# Mainboard-mbed.net
KiCad netlist of a schematic drawn in Altium Designer
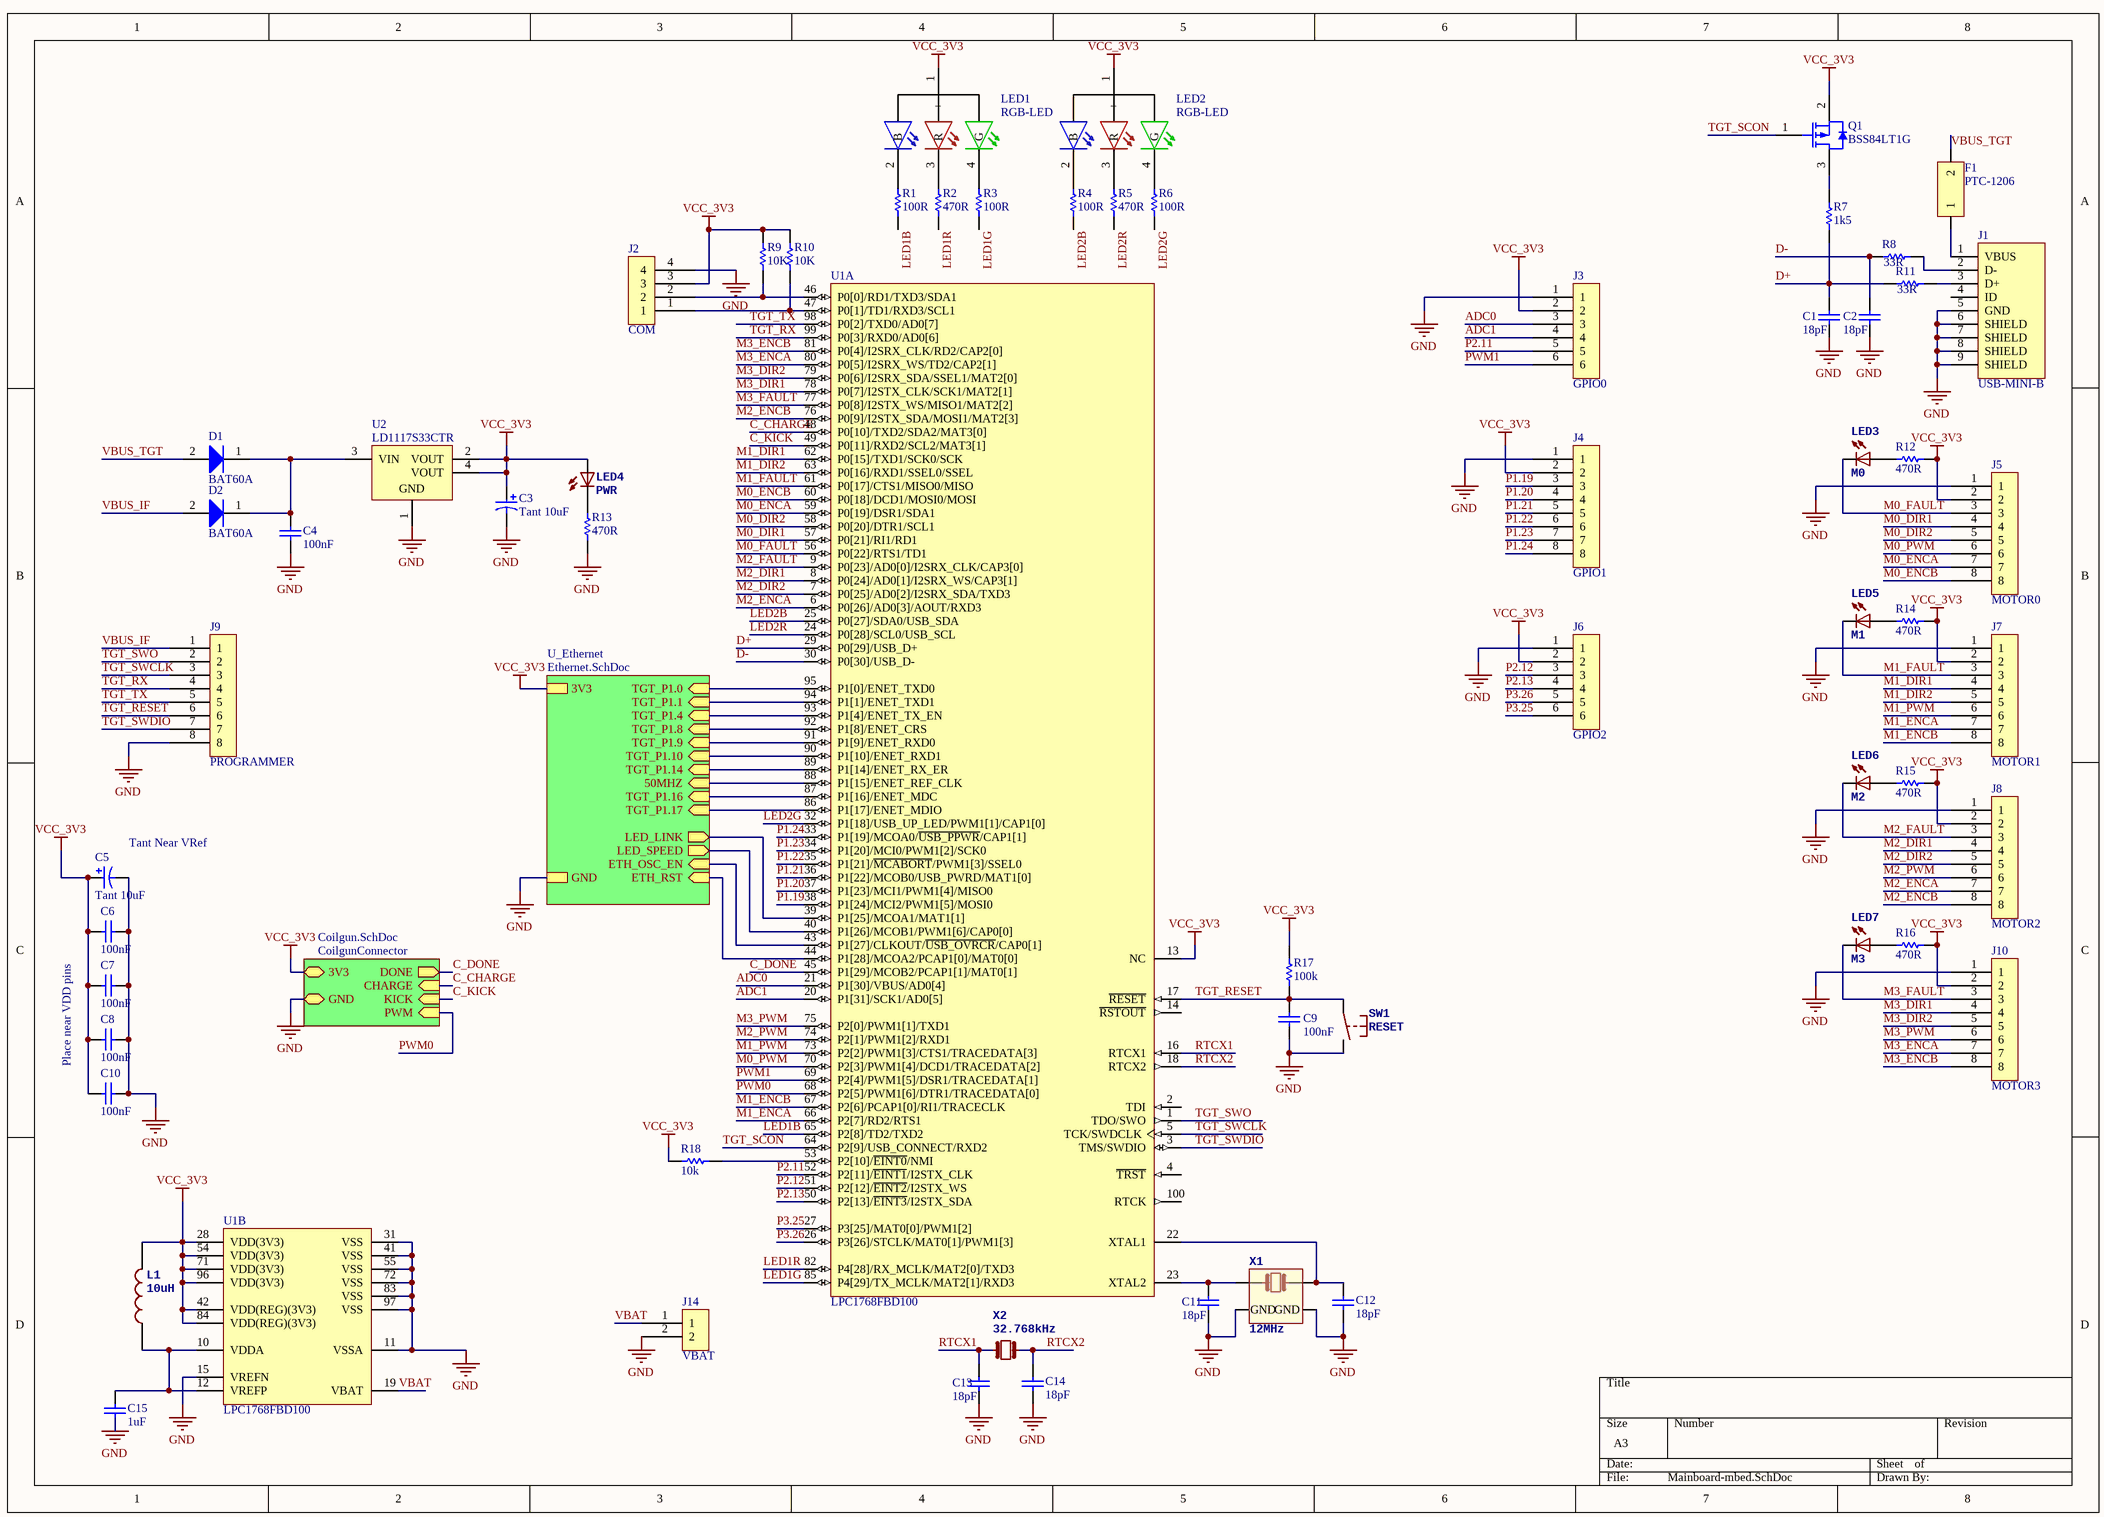
[diagram p0: Mainboard-mbed.SchDoc]

(export (version "E")
  (design (tool "Eeschema 10.0.6"))
  (components
    (comp (ref "C1")
      (value "18pF")
      (footprint "CAPC0603(1608)100_L")
      (description "0603 (1608 Metric) Chip Capacitor")
      (fields (field (name "Comment") "CAP0603"))
      (libsource (lib "Altium Content Vault") (part "CMP-1590-00005-1"))
    )
    (comp (ref "C2")
      (value "18pF")
      (footprint "CAPC0603(1608)100_L")
      (description "0603 (1608 Metric) Chip Capacitor")
      (fields (field (name "Comment") "CAP0603"))
      (libsource (lib "Altium Content Vault") (part "CMP-1590-00005-1"))
    )
    (comp (ref "C3")
      (value "Tant 10uF")
      (footprint "CAPMP3528X12N")
      (libsource (lib "passive") (part "cap_pol"))
    )
    (comp (ref "C4")
      (value "100nF")
      (footprint "CAPC0603(1608)100_L")
      (description "0603 (1608 Metric) Chip Capacitor")
      (fields (field (name "Comment") "CAP0603"))
      (libsource (lib "Altium Content Vault") (part "CMP-1590-00005-1"))
    )
    (comp (ref "C5")
      (value "Tant 10uF")
      (footprint "CAPMP3528X12N")
      (libsource (lib "passive") (part "cap_pol"))
    )
    (comp (ref "C6")
      (value "100nF")
      (footprint "CAPC0603(1608)100_L")
      (description "CAP 100nF 10V ±5% 0603 (1608 Metric) Thickness 1mm SMD")
      (fields (field (name "TOLERANCE") "Â±5%"))
      (libsource (lib "Altium Content Vault") (part "CMP-1035-02579-1"))
    )
    (comp (ref "C7")
      (value "100nF")
      (footprint "CAPC0603(1608)100_L")
      (description "CAP 100nF 10V ±5% 0603 (1608 Metric) Thickness 1mm SMD")
      (fields (field (name "TOLERANCE") "Â±5%"))
      (libsource (lib "Altium Content Vault") (part "CMP-1035-02579-1"))
    )
    (comp (ref "C8")
      (value "100nF")
      (footprint "CAPC0603(1608)100_L")
      (description "CAP 100nF 10V ±5% 0603 (1608 Metric) Thickness 1mm SMD")
      (fields (field (name "TOLERANCE") "Â±5%"))
      (libsource (lib "Altium Content Vault") (part "CMP-1035-02579-1"))
    )
    (comp (ref "C9")
      (value "100nF")
      (footprint "CAPC0603(1608)100_L")
      (description "0603 (1608 Metric) Chip Capacitor")
      (fields (field (name "Comment") "CAP0603"))
      (libsource (lib "Altium Content Vault") (part "CMP-1590-00005-1"))
    )
    (comp (ref "C10")
      (value "100nF")
      (footprint "CAPC0603(1608)100_L")
      (description "CAP 100nF 10V ±5% 0603 (1608 Metric) Thickness 1mm SMD")
      (fields (field (name "TOLERANCE") "Â±5%"))
      (libsource (lib "Altium Content Vault") (part "CMP-1035-02579-1"))
    )
    (comp (ref "C11")
      (value "18pF")
      (footprint "CAPC0603(1608)100_L")
      (description "0603 (1608 Metric) Chip Capacitor")
      (fields (field (name "Comment") "CAP0603"))
      (libsource (lib "Altium Content Vault") (part "CMP-1590-00005-1"))
    )
    (comp (ref "C12")
      (value "18pF")
      (footprint "CAPC0603(1608)100_L")
      (description "0603 (1608 Metric) Chip Capacitor")
      (fields (field (name "Comment") "CAP0603"))
      (libsource (lib "Altium Content Vault") (part "CMP-1590-00005-1"))
    )
    (comp (ref "C13")
      (value "18pF")
      (footprint "CAPC0603(1608)100_L")
      (description "0603 (1608 Metric) Chip Capacitor")
      (fields (field (name "Comment") "CAP0603"))
      (libsource (lib "Altium Content Vault") (part "CMP-1590-00005-1"))
    )
    (comp (ref "C14")
      (value "18pF")
      (footprint "CAPC0603(1608)100_L")
      (description "0603 (1608 Metric) Chip Capacitor")
      (fields (field (name "Comment") "CAP0603"))
      (libsource (lib "Altium Content Vault") (part "CMP-1590-00005-1"))
    )
    (comp (ref "C15")
      (value "1uF")
      (footprint "CAPC0603(1608)100_L")
      (description "0603 (1608 Metric) Chip Capacitor")
      (fields (field (name "Comment") "CAP0603"))
      (libsource (lib "Altium Content Vault") (part "CMP-1590-00005-1"))
    )
    (comp (ref "D1")
      (value "BAT60A")
      (footprint "INF-SOD323_V")
      (description "Silicon Schottky Diode, -55 to 85 degC, SOD323, Reel, Green")
      (fields (field (name "MANUFACTURER") "Infineon"))
      (libsource (lib "Altium Content Vault") (part "INF-D_K1A2-2"))
    )
    (comp (ref "D2")
      (value "BAT60A")
      (footprint "INF-SOD323_V")
      (description "Silicon Schottky Diode, -55 to 85 degC, SOD323, Reel, Green")
      (fields (field (name "MANUFACTURER") "Infineon"))
      (libsource (lib "Altium Content Vault") (part "INF-D_K1A2-2"))
    )
    (comp (ref "F1") (value "PTC-1206") (footprint "PTC-1206") (libsource (lib "power") (part "PTC-1206")))
    (comp (ref "J1")
      (value "USB-MINI-B")
      (footprint "USB-B-MINI")
      (libsource (lib "connectors") (part "USB-B-MINI"))
    )
    (comp (ref "J2")
      (value "COM")
      (footprint "MICRO-MATCH-4")
      (libsource (lib "connectors") (part "HEADER-4"))
    )
    (comp (ref "J3")
      (value "GPIO0")
      (footprint "MICRO-MATCH-6")
      (libsource (lib "connectors") (part "HEADER-6"))
    )
    (comp (ref "J4")
      (value "GPIO1")
      (footprint "MICRO-MATCH-8")
      (libsource (lib "connectors") (part "HEADER-8"))
    )
    (comp (ref "J5")
      (value "MOTOR0")
      (footprint "MICRO-MATCH-8")
      (libsource (lib "connectors") (part "HEADER-8"))
    )
    (comp (ref "J6")
      (value "GPIO2")
      (footprint "MICRO-MATCH-6")
      (libsource (lib "connectors") (part "HEADER-6"))
    )
    (comp (ref "J7")
      (value "MOTOR1")
      (footprint "MICRO-MATCH-8")
      (libsource (lib "connectors") (part "HEADER-8"))
    )
    (comp (ref "J8")
      (value "MOTOR2")
      (footprint "MICRO-MATCH-8")
      (libsource (lib "connectors") (part "HEADER-8"))
    )
    (comp (ref "J9")
      (value "PROGRAMMER")
      (footprint "MICRO-MATCH-8")
      (libsource (lib "connectors") (part "HEADER-8"))
    )
    (comp (ref "J10")
      (value "MOTOR3")
      (footprint "MICRO-MATCH-8")
      (libsource (lib "connectors") (part "HEADER-8"))
    )
    (comp (ref "J14")
      (value "VBAT")
      (footprint "PIN-HEADER-2")
      (libsource (lib "connectors") (part "HEADER-2"))
    )
    (comp (ref "L1") (value "10uH") (footprint "0603") (libsource (lib "mbed-HDK") (part "L")))
    (comp (ref "LED1") (value "RGB-LED") (footprint "RGB-LED") (libsource (lib "misc") (part "RGB-LED")))
    (comp (ref "LED2") (value "RGB-LED") (footprint "RGB-LED") (libsource (lib "misc") (part "RGB-LED")))
    (comp (ref "LED3") (value "M0") (footprint "CHIPLED_0603") (libsource (lib "mbed-HDK") (part "LED0603")))
    (comp (ref "LED4") (value "PWR") (footprint "CHIPLED_0603") (libsource (lib "mbed-HDK") (part "LED0603")))
    (comp (ref "LED5") (value "M1") (footprint "CHIPLED_0603") (libsource (lib "mbed-HDK") (part "LED0603")))
    (comp (ref "LED6") (value "M2") (footprint "CHIPLED_0603") (libsource (lib "mbed-HDK") (part "LED0603")))
    (comp (ref "LED7") (value "M3") (footprint "CHIPLED_0603") (libsource (lib "mbed-HDK") (part "LED0603")))
    (comp (ref "Q1")
      (value "BSS84LT1G")
      (footprint "ONSC-SOT-23-3-318-08_V")
      (description "Power MOSFET Single P-Channel, -50 V, 10 Ohm, 3-Pin SOT-23, Pb-Free, Tape and Reel")
      (fields (field (name "MANUFACTURER") "On Semiconductor"))
      (libsource (lib "Altium Content Vault") (part "CMP-1058-00762-1"))
    )
    (comp (ref "R1")
      (value "100R")
      (footprint "RESC0603(1608)_L")
      (fields (field (name "TOLERANCE") "5 %") (field (name "POWER") "0.1 W"))
      (libsource (lib "Altium Content Vault") (part "CMP-1012-00050-1"))
    )
    (comp (ref "R2")
      (value "470R")
      (footprint "RESC0603(1608)_L")
      (description "470R 0.1W 5% 0603 (1608 Metric)  SMD")
      (fields (field (name "TOLERANCE") "5 %") (field (name "POWER") "0.1 W"))
      (libsource (lib "Altium Content Vault") (part "CMP-1012-00066-1"))
    )
    (comp (ref "R3")
      (value "100R")
      (footprint "RESC0603(1608)_L")
      (fields (field (name "TOLERANCE") "5 %") (field (name "POWER") "0.1 W"))
      (libsource (lib "Altium Content Vault") (part "CMP-1012-00050-1"))
    )
    (comp (ref "R4")
      (value "100R")
      (footprint "RESC0603(1608)_L")
      (fields (field (name "TOLERANCE") "5 %") (field (name "POWER") "0.1 W"))
      (libsource (lib "Altium Content Vault") (part "CMP-1012-00050-1"))
    )
    (comp (ref "R5")
      (value "470R")
      (footprint "RESC0603(1608)_L")
      (description "470R 0.1W 5% 0603 (1608 Metric)  SMD")
      (fields (field (name "TOLERANCE") "5 %") (field (name "POWER") "0.1 W"))
      (libsource (lib "Altium Content Vault") (part "CMP-1012-00066-1"))
    )
    (comp (ref "R6")
      (value "100R")
      (footprint "RESC0603(1608)_L")
      (fields (field (name "TOLERANCE") "5 %") (field (name "POWER") "0.1 W"))
      (libsource (lib "Altium Content Vault") (part "CMP-1012-00050-1"))
    )
    (comp (ref "R7")
      (value "1k5")
      (footprint "RESC0603(1608)_L")
      (description "0603 (1608 Metric) Chip Resistor")
      (fields (field (name "Comment") "RES0603"))
      (libsource (lib "Altium Content Vault") (part "CMP-1591-00001-1"))
    )
    (comp (ref "R8")
      (value "33R")
      (footprint "RESC0603(1608)_L")
      (description "0603 (1608 Metric) Chip Resistor")
      (fields (field (name "Comment") "RES0603"))
      (libsource (lib "Altium Content Vault") (part "CMP-1591-00001-1"))
    )
    (comp (ref "R9")
      (value "10K")
      (footprint "RESC0603(1608)_L")
      (fields (field (name "TOLERANCE") "5 %") (field (name "POWER") "0.1 W"))
      (libsource (lib "Altium Content Vault") (part "CMP-1012-00098-1"))
    )
    (comp (ref "R10")
      (value "10K")
      (footprint "RESC0603(1608)_L")
      (fields (field (name "TOLERANCE") "5 %") (field (name "POWER") "0.1 W"))
      (libsource (lib "Altium Content Vault") (part "CMP-1012-00098-1"))
    )
    (comp (ref "R11")
      (value "33R")
      (footprint "RESC0603(1608)_L")
      (description "0603 (1608 Metric) Chip Resistor")
      (fields (field (name "Comment") "RES0603"))
      (libsource (lib "Altium Content Vault") (part "CMP-1591-00001-1"))
    )
    (comp (ref "R12")
      (value "470R")
      (footprint "RESC0603(1608)_N")
      (description "470R 0.1W 5% 0603 (1608 Metric)  SMD")
      (fields (field (name "TOLERANCE") "5 %") (field (name "POWER") "0.1 W"))
      (libsource (lib "Altium Content Vault") (part "CMP-1012-00066-1"))
    )
    (comp (ref "R13")
      (value "470R")
      (footprint "RESC0603(1608)_L")
      (description "470R 0.1W 5% 0603 (1608 Metric)  SMD")
      (fields (field (name "TOLERANCE") "5 %") (field (name "POWER") "0.1 W"))
      (libsource (lib "Altium Content Vault") (part "CMP-1012-00066-1"))
    )
    (comp (ref "R14")
      (value "470R")
      (footprint "RESC0603(1608)_N")
      (description "470R 0.1W 5% 0603 (1608 Metric)  SMD")
      (fields (field (name "TOLERANCE") "5 %") (field (name "POWER") "0.1 W"))
      (libsource (lib "Altium Content Vault") (part "CMP-1012-00066-1"))
    )
    (comp (ref "R15")
      (value "470R")
      (footprint "RESC0603(1608)_N")
      (description "470R 0.1W 5% 0603 (1608 Metric)  SMD")
      (fields (field (name "TOLERANCE") "5 %") (field (name "POWER") "0.1 W"))
      (libsource (lib "Altium Content Vault") (part "CMP-1012-00066-1"))
    )
    (comp (ref "R16")
      (value "470R")
      (footprint "RESC0603(1608)_N")
      (description "470R 0.1W 5% 0603 (1608 Metric)  SMD")
      (fields (field (name "TOLERANCE") "5 %") (field (name "POWER") "0.1 W"))
      (libsource (lib "Altium Content Vault") (part "CMP-1012-00066-1"))
    )
    (comp (ref "R17")
      (value "100k")
      (footprint "RESC0603(1608)_L")
      (description "0603 (1608 Metric) Chip Resistor")
      (fields (field (name "Comment") "RES0603"))
      (libsource (lib "Altium Content Vault") (part "CMP-1591-00001-1"))
    )
    (comp (ref "R18")
      (value "10k")
      (footprint "RESC0603(1608)_L")
      (description "0603 (1608 Metric) Chip Resistor")
      (fields (field (name "Comment") "RES0603"))
      (libsource (lib "Altium Content Vault") (part "CMP-1591-00001-1"))
    )
    (comp (ref "SW1") (value "RESET") (footprint "DTSM-32S-B") (libsource (lib "mbed-HDK") (part "SPST")))
    (comp (ref "U1")
      (value "LPC1768FBD100")
      (footprint "SOT407-1_L")
      (libsource (lib "Altium Content Vault") (part "MC-32B-LPC1769_68_66-SQ100"))
    )
    (comp (ref "U2")
      (value "LD1117S33CTR")
      (footprint "SOT-223_N")
      (description "Fixed Low Drop Positive Voltage Regulator, 3.3V, 4-Pin SOT-223, Tape and Reel")
      (libsource (lib "Altium Content Vault") (part "PM-REG-LD1117-SOT4"))
    )
    (comp (ref "X1") (value "12MHz") (footprint "3.2X.2.5") (libsource (lib "mbed-HDK") (part "Q_3.2X2.5")))
    (comp (ref "X2") (value "32.768kHz") (footprint "FC135") (libsource (lib "mbed-HDK") (part "Q_FC135")))
  )
  (nets
    (net (code "1") (name "/50MHZ") (class "Default")
      (node (ref "U1") (pin "88") (pinfunction "P1[15]/ENET_REF_CLK_88") (pintype "bidirectional"))
    )
    (net (code "2") (name "/ADC0") (class "Default")
      (node (ref "J3") (pin "3") (pinfunction "3_3") (pintype "passive"))
      (node (ref "U1") (pin "21") (pinfunction "P1[30]/VBUS/AD0[4]_21") (pintype "bidirectional"))
    )
    (net (code "3") (name "/ADC1") (class "Default")
      (node (ref "J3") (pin "4") (pinfunction "4_4") (pintype "passive"))
      (node (ref "U1") (pin "20") (pinfunction "P1[31]/SCK1/AD0[5]_20") (pintype "bidirectional"))
    )
    (net (code "4") (name "/C_CHARGE") (class "Default")
      (node (ref "U1") (pin "48") (pinfunction "P0[10]/TXD2/SDA2/MAT3[0]_48") (pintype "bidirectional"))
    )
    (net (code "5") (name "/C_DONE") (class "Default")
      (node (ref "U1") (pin "45") (pinfunction "P1[29]/MCOB2/PCAP1[1]/MAT0[1]_45") (pintype "bidirectional"))
    )
    (net (code "6") (name "/C_KICK") (class "Default")
      (node (ref "U1") (pin "49") (pinfunction "P0[11]/RXD2/SCL2/MAT3[1]_49") (pintype "bidirectional"))
    )
    (net (code "7") (name "/D+") (class "Default")
      (node (ref "C1") (pin "1") (pinfunction "1_1") (pintype "passive"))
      (node (ref "R11") (pin "1") (pinfunction "1_1") (pintype "passive"))
      (node (ref "R7") (pin "1") (pinfunction "1_1") (pintype "passive"))
      (node (ref "U1") (pin "29") (pinfunction "P0[29]/USB_D+_29") (pintype "bidirectional"))
    )
    (net (code "8") (name "/D-") (class "Default")
      (node (ref "C2") (pin "1") (pinfunction "1_1") (pintype "passive"))
      (node (ref "R8") (pin "1") (pinfunction "1_1") (pintype "passive"))
      (node (ref "U1") (pin "30") (pinfunction "P0[30]/USB_D-_30") (pintype "bidirectional"))
    )
    (net (code "9") (name "/ETH_OSC_EN") (class "Default")
      (node (ref "U1") (pin "43") (pinfunction "P1[27]/CLKOUT/~{USB_OVRCR}/CAP0[1]_43") (pintype "bidirectional"))
    )
    (net (code "10") (name "/ETH_RST") (class "Default")
      (node (ref "U1") (pin "44") (pinfunction "P1[28]/MCOA2/PCAP1[0]/MAT0[0]_44") (pintype "bidirectional"))
    )
    (net (code "11") (name "/LED1B") (class "Default")
      (node (ref "R1") (pin "2") (pinfunction "2_2") (pintype "passive"))
      (node (ref "U1") (pin "65") (pinfunction "P2[8]/TD2/TXD2_65") (pintype "bidirectional"))
    )
    (net (code "12") (name "/LED1G") (class "Default")
      (node (ref "R3") (pin "2") (pinfunction "2_2") (pintype "passive"))
      (node (ref "U1") (pin "85") (pinfunction "P4[29]/TX_MCLK/MAT2[1]/RXD3_85") (pintype "bidirectional"))
    )
    (net (code "13") (name "/LED1R") (class "Default")
      (node (ref "R2") (pin "1") (pinfunction "1_1") (pintype "passive"))
      (node (ref "U1") (pin "82") (pinfunction "P4[28]/RX_MCLK/MAT2[0]/TXD3_82") (pintype "bidirectional"))
    )
    (net (code "14") (name "/LED2B") (class "Default")
      (node (ref "R4") (pin "2") (pinfunction "2_2") (pintype "passive"))
      (node (ref "U1") (pin "25") (pinfunction "P0[27]/SDA0/USB_SDA_25") (pintype "bidirectional"))
    )
    (net (code "15") (name "/LED2G") (class "Default")
      (node (ref "R6") (pin "2") (pinfunction "2_2") (pintype "passive"))
      (node (ref "U1") (pin "32") (pinfunction "P1[18]/USB_UP_LED/PWM1[1]/CAP1[0]_32") (pintype "bidirectional"))
    )
    (net (code "16") (name "/LED2R") (class "Default")
      (node (ref "R5") (pin "1") (pinfunction "1_1") (pintype "passive"))
      (node (ref "U1") (pin "24") (pinfunction "P0[28]/SCL0/USB_SCL_24") (pintype "bidirectional"))
    )
    (net (code "17") (name "/LED_LINK") (class "Default")
      (node (ref "U1") (pin "39") (pinfunction "P1[25]/MCOA1/MAT1[1]_39") (pintype "bidirectional"))
    )
    (net (code "18") (name "/LED_SPEED") (class "Default")
      (node (ref "U1") (pin "40") (pinfunction "P1[26]/MCOB1/PWM1[6]/CAP0[0]_40") (pintype "bidirectional"))
    )
    (net (code "19") (name "/M0_DIR1") (class "Default")
      (node (ref "J5") (pin "4") (pinfunction "4_4") (pintype "passive"))
      (node (ref "U1") (pin "57") (pinfunction "P0[21]/RI1/RD1_57") (pintype "bidirectional"))
    )
    (net (code "20") (name "/M0_DIR2") (class "Default")
      (node (ref "J5") (pin "5") (pinfunction "5_5") (pintype "passive"))
      (node (ref "U1") (pin "58") (pinfunction "P0[20]/DTR1/SCL1_58") (pintype "bidirectional"))
    )
    (net (code "21") (name "/M0_ENCA") (class "Default")
      (node (ref "J5") (pin "7") (pinfunction "7_7") (pintype "passive"))
      (node (ref "U1") (pin "59") (pinfunction "P0[19]/DSR1/SDA1_59") (pintype "bidirectional"))
    )
    (net (code "22") (name "/M0_ENCB") (class "Default")
      (node (ref "J5") (pin "8") (pinfunction "8_8") (pintype "passive"))
      (node (ref "U1") (pin "60") (pinfunction "P0[18]/DCD1/MOSI0/MOSI_60") (pintype "bidirectional"))
    )
    (net (code "23") (name "/M0_FAULT") (class "Default")
      (node (ref "J5") (pin "3") (pinfunction "3_3") (pintype "passive"))
      (node (ref "LED3") (pin "C") (pinfunction "C_C") (pintype "passive"))
      (node (ref "U1") (pin "56") (pinfunction "P0[22]/RTS1/TD1_56") (pintype "bidirectional"))
    )
    (net (code "24") (name "/M0_PWM") (class "Default")
      (node (ref "J5") (pin "6") (pinfunction "6_6") (pintype "passive"))
      (node (ref "U1") (pin "70") (pinfunction "P2[3]/PWM1[4]/DCD1/TRACEDATA[2]_70") (pintype "bidirectional"))
    )
    (net (code "25") (name "/M1_DIR1") (class "Default")
      (node (ref "J7") (pin "4") (pinfunction "4_4") (pintype "passive"))
      (node (ref "U1") (pin "62") (pinfunction "P0[15]/TXD1/SCK0/SCK_62") (pintype "bidirectional"))
    )
    (net (code "26") (name "/M1_DIR2") (class "Default")
      (node (ref "J7") (pin "5") (pinfunction "5_5") (pintype "passive"))
      (node (ref "U1") (pin "63") (pinfunction "P0[16]/RXD1/SSEL0/SSEL_63") (pintype "bidirectional"))
    )
    (net (code "27") (name "/M1_ENCA") (class "Default")
      (node (ref "J7") (pin "7") (pinfunction "7_7") (pintype "passive"))
      (node (ref "U1") (pin "66") (pinfunction "P2[7]/RD2/RTS1_66") (pintype "bidirectional"))
    )
    (net (code "28") (name "/M1_ENCB") (class "Default")
      (node (ref "J7") (pin "8") (pinfunction "8_8") (pintype "passive"))
      (node (ref "U1") (pin "67") (pinfunction "P2[6]/PCAP1[0]/RI1/TRACECLK_67") (pintype "bidirectional"))
    )
    (net (code "29") (name "/M1_FAULT") (class "Default")
      (node (ref "J7") (pin "3") (pinfunction "3_3") (pintype "passive"))
      (node (ref "LED5") (pin "C") (pinfunction "C_C") (pintype "passive"))
      (node (ref "U1") (pin "61") (pinfunction "P0[17]/CTS1/MISO0/MISO_61") (pintype "bidirectional"))
    )
    (net (code "30") (name "/M1_PWM") (class "Default")
      (node (ref "J7") (pin "6") (pinfunction "6_6") (pintype "passive"))
      (node (ref "U1") (pin "73") (pinfunction "P2[2]/PWM1[3]/CTS1/TRACEDATA[3]_73") (pintype "bidirectional"))
    )
    (net (code "31") (name "/M2_DIR1") (class "Default")
      (node (ref "J8") (pin "4") (pinfunction "4_4") (pintype "passive"))
      (node (ref "U1") (pin "8") (pinfunction "P0[24]/AD0[1]/I2SRX_WS/CAP3[1]_8") (pintype "bidirectional"))
    )
    (net (code "32") (name "/M2_DIR2") (class "Default")
      (node (ref "J8") (pin "5") (pinfunction "5_5") (pintype "passive"))
      (node (ref "U1") (pin "7") (pinfunction "P0[25]/AD0[2]/I2SRX_SDA/TXD3_7") (pintype "bidirectional"))
    )
    (net (code "33") (name "/M2_ENCA") (class "Default")
      (node (ref "J8") (pin "7") (pinfunction "7_7") (pintype "passive"))
      (node (ref "U1") (pin "6") (pinfunction "P0[26]/AD0[3]/AOUT/RXD3_6") (pintype "bidirectional"))
    )
    (net (code "34") (name "/M2_ENCB") (class "Default")
      (node (ref "J8") (pin "8") (pinfunction "8_8") (pintype "passive"))
      (node (ref "U1") (pin "76") (pinfunction "P0[9]/I2STX_SDA/MOSI1/MAT2[3]_76") (pintype "bidirectional"))
    )
    (net (code "35") (name "/M2_FAULT") (class "Default")
      (node (ref "J8") (pin "3") (pinfunction "3_3") (pintype "passive"))
      (node (ref "LED6") (pin "C") (pinfunction "C_C") (pintype "passive"))
      (node (ref "U1") (pin "9") (pinfunction "P0[23]/AD0[0]/I2SRX_CLK/CAP3[0]_9") (pintype "bidirectional"))
    )
    (net (code "36") (name "/M2_PWM") (class "Default")
      (node (ref "J8") (pin "6") (pinfunction "6_6") (pintype "passive"))
      (node (ref "U1") (pin "74") (pinfunction "P2[1]/PWM1[2]/RXD1_74") (pintype "bidirectional"))
    )
    (net (code "37") (name "/M3_DIR1") (class "Default")
      (node (ref "J10") (pin "4") (pinfunction "4_4") (pintype "passive"))
      (node (ref "U1") (pin "78") (pinfunction "P0[7]/I2STX_CLK/SCK1/MAT2[1]_78") (pintype "bidirectional"))
    )
    (net (code "38") (name "/M3_DIR2") (class "Default")
      (node (ref "J10") (pin "5") (pinfunction "5_5") (pintype "passive"))
      (node (ref "U1") (pin "79") (pinfunction "P0[6]/I2SRX_SDA/SSEL1/MAT2[0]_79") (pintype "bidirectional"))
    )
    (net (code "39") (name "/M3_ENCA") (class "Default")
      (node (ref "J10") (pin "7") (pinfunction "7_7") (pintype "passive"))
      (node (ref "U1") (pin "80") (pinfunction "P0[5]/I2SRX_WS/TD2/CAP2[1]_80") (pintype "bidirectional"))
    )
    (net (code "40") (name "/M3_ENCB") (class "Default")
      (node (ref "J10") (pin "8") (pinfunction "8_8") (pintype "passive"))
      (node (ref "U1") (pin "81") (pinfunction "P0[4]/I2SRX_CLK/RD2/CAP2[0]_81") (pintype "bidirectional"))
    )
    (net (code "41") (name "/M3_FAULT") (class "Default")
      (node (ref "J10") (pin "3") (pinfunction "3_3") (pintype "passive"))
      (node (ref "LED7") (pin "C") (pinfunction "C_C") (pintype "passive"))
      (node (ref "U1") (pin "77") (pinfunction "P0[8]/I2STX_WS/MISO1/MAT2[2]_77") (pintype "bidirectional"))
    )
    (net (code "42") (name "/M3_PWM") (class "Default")
      (node (ref "J10") (pin "6") (pinfunction "6_6") (pintype "passive"))
      (node (ref "U1") (pin "75") (pinfunction "P2[0]/PWM1[1]/TXD1_75") (pintype "bidirectional"))
    )
    (net (code "43") (name "/P1.19") (class "Default")
      (node (ref "J4") (pin "3") (pinfunction "3_3") (pintype "passive"))
      (node (ref "U1") (pin "38") (pinfunction "P1[24]/MCI2/PWM1[5]/MOSI0_38") (pintype "bidirectional"))
    )
    (net (code "44") (name "/P1.20") (class "Default")
      (node (ref "J4") (pin "4") (pinfunction "4_4") (pintype "passive"))
      (node (ref "U1") (pin "37") (pinfunction "P1[23]/MCI1/PWM1[4]/MISO0_37") (pintype "bidirectional"))
    )
    (net (code "45") (name "/P1.21") (class "Default")
      (node (ref "J4") (pin "5") (pinfunction "5_5") (pintype "passive"))
      (node (ref "U1") (pin "36") (pinfunction "P1[22]/MCOB0/USB_PWRD/MAT1[0]_36") (pintype "bidirectional"))
    )
    (net (code "46") (name "/P1.22") (class "Default")
      (node (ref "J4") (pin "6") (pinfunction "6_6") (pintype "passive"))
      (node (ref "U1") (pin "35") (pinfunction "P1[21]/~{MCABORT}/PWM1[3]/SSEL0_35") (pintype "bidirectional"))
    )
    (net (code "47") (name "/P1.23") (class "Default")
      (node (ref "J4") (pin "7") (pinfunction "7_7") (pintype "passive"))
      (node (ref "U1") (pin "34") (pinfunction "P1[20]/MCI0/PWM1[2]/SCK0_34") (pintype "bidirectional"))
    )
    (net (code "48") (name "/P1.24") (class "Default")
      (node (ref "J4") (pin "8") (pinfunction "8_8") (pintype "passive"))
      (node (ref "U1") (pin "33") (pinfunction "P1[19]/MCOA0/~{USB_PPWR}/CAP1[1]_33") (pintype "bidirectional"))
    )
    (net (code "49") (name "/P2.11") (class "Default")
      (node (ref "J3") (pin "5") (pinfunction "5_5") (pintype "passive"))
      (node (ref "U1") (pin "52") (pinfunction "P2[11]/~{EINT1}/I2STX_CLK_52") (pintype "bidirectional"))
    )
    (net (code "50") (name "/P2.12") (class "Default")
      (node (ref "J6") (pin "3") (pinfunction "3_3") (pintype "passive"))
      (node (ref "U1") (pin "51") (pinfunction "P2[12]/~{EINT2}/I2STX_WS_51") (pintype "bidirectional"))
    )
    (net (code "51") (name "/P2.13") (class "Default")
      (node (ref "J6") (pin "4") (pinfunction "4_4") (pintype "passive"))
      (node (ref "U1") (pin "50") (pinfunction "P2[13]/~{EINT3}/I2STX_SDA_50") (pintype "bidirectional"))
    )
    (net (code "52") (name "/P3.25") (class "Default")
      (node (ref "J6") (pin "6") (pinfunction "6_6") (pintype "passive"))
      (node (ref "U1") (pin "27") (pinfunction "P3[25]/MAT0[0]/PWM1[2]_27") (pintype "bidirectional"))
    )
    (net (code "53") (name "/P3.26") (class "Default")
      (node (ref "J6") (pin "5") (pinfunction "5_5") (pintype "passive"))
      (node (ref "U1") (pin "26") (pinfunction "P3[26]/STCLK/MAT0[1]/PWM1[3]_26") (pintype "bidirectional"))
    )
    (net (code "54") (name "/PWM0") (class "Default")
      (node (ref "U1") (pin "68") (pinfunction "P2[5]/PWM1[6]/DTR1/TRACEDATA[0]_68") (pintype "bidirectional"))
    )
    (net (code "55") (name "/PWM1") (class "Default")
      (node (ref "J3") (pin "6") (pinfunction "6_6") (pintype "passive"))
      (node (ref "U1") (pin "69") (pinfunction "P2[4]/PWM1[5]/DSR1/TRACEDATA[1]_69") (pintype "bidirectional"))
    )
    (net (code "56") (name "/RTCX1") (class "Default")
      (node (ref "C13") (pin "1") (pinfunction "1_1") (pintype "passive"))
      (node (ref "U1") (pin "16") (pinfunction "RTCX1_16") (pintype "input"))
      (node (ref "X2") (pin "X2") (pinfunction "2_X2") (pintype "passive"))
    )
    (net (code "57") (name "/RTCX2") (class "Default")
      (node (ref "C14") (pin "1") (pinfunction "1_1") (pintype "passive"))
      (node (ref "U1") (pin "18") (pinfunction "RTCX2_18") (pintype "output"))
      (node (ref "X2") (pin "X1") (pinfunction "1_X1") (pintype "passive"))
    )
    (net (code "58") (name "/TGT_P1.0") (class "Default")
      (node (ref "U1") (pin "95") (pinfunction "P1[0]/ENET_TXD0_95") (pintype "bidirectional"))
    )
    (net (code "59") (name "/TGT_P1.1") (class "Default")
      (node (ref "U1") (pin "94") (pinfunction "P1[1]/ENET_TXD1_94") (pintype "bidirectional"))
    )
    (net (code "60") (name "/TGT_P1.4") (class "Default")
      (node (ref "U1") (pin "93") (pinfunction "P1[4]/ENET_TX_EN_93") (pintype "bidirectional"))
    )
    (net (code "61") (name "/TGT_P1.8") (class "Default")
      (node (ref "U1") (pin "92") (pinfunction "P1[8]/ENET_CRS_92") (pintype "bidirectional"))
    )
    (net (code "62") (name "/TGT_P1.9") (class "Default")
      (node (ref "U1") (pin "91") (pinfunction "P1[9]/ENET_RXD0_91") (pintype "bidirectional"))
    )
    (net (code "63") (name "/TGT_P1.10") (class "Default")
      (node (ref "U1") (pin "90") (pinfunction "P1[10]/ENET_RXD1_90") (pintype "bidirectional"))
    )
    (net (code "64") (name "/TGT_P1.14") (class "Default")
      (node (ref "U1") (pin "89") (pinfunction "P1[14]/ENET_RX_ER_89") (pintype "bidirectional"))
    )
    (net (code "65") (name "/TGT_P1.16") (class "Default")
      (node (ref "U1") (pin "87") (pinfunction "P1[16]/ENET_MDC_87") (pintype "bidirectional"))
    )
    (net (code "66") (name "/TGT_P1.17") (class "Default")
      (node (ref "U1") (pin "86") (pinfunction "P1[17]/ENET_MDIO_86") (pintype "bidirectional"))
    )
    (net (code "67") (name "/TGT_RESET") (class "Default")
      (node (ref "C9") (pin "1") (pinfunction "1_1") (pintype "passive"))
      (node (ref "J9") (pin "6") (pinfunction "6_6") (pintype "passive"))
      (node (ref "R17") (pin "1") (pinfunction "1_1") (pintype "passive"))
      (node (ref "SW1") (pin "P$1") (pinfunction "P_P$1") (pintype "passive"))
      (node (ref "U1") (pin "17") (pinfunction "~{RESET}_17") (pintype "input"))
    )
    (net (code "68") (name "/TGT_RX") (class "Default")
      (node (ref "J9") (pin "4") (pinfunction "4_4") (pintype "passive"))
      (node (ref "U1") (pin "99") (pinfunction "P0[3]/RXD0/AD0[6]_99") (pintype "bidirectional"))
    )
    (net (code "69") (name "/TGT_SCON") (class "Default")
      (node (ref "Q1") (pin "1") (pinfunction "G_1") (pintype "passive"))
      (node (ref "U1") (pin "64") (pinfunction "P2[9]/USB_CONNECT/RXD2_64") (pintype "bidirectional"))
    )
    (net (code "70") (name "/TGT_SWCLK") (class "Default")
      (node (ref "J9") (pin "3") (pinfunction "3_3") (pintype "passive"))
      (node (ref "U1") (pin "5") (pinfunction "TCK/SWDCLK_5") (pintype "input"))
    )
    (net (code "71") (name "/TGT_SWDIO") (class "Default")
      (node (ref "J9") (pin "7") (pinfunction "7_7") (pintype "passive"))
      (node (ref "U1") (pin "3") (pinfunction "TMS/SWDIO_3") (pintype "bidirectional"))
    )
    (net (code "72") (name "/TGT_SWO") (class "Default")
      (node (ref "J9") (pin "2") (pinfunction "2_2") (pintype "passive"))
      (node (ref "U1") (pin "1") (pinfunction "TDO/SWO_1") (pintype "output"))
    )
    (net (code "73") (name "/TGT_TX") (class "Default")
      (node (ref "J9") (pin "5") (pinfunction "5_5") (pintype "passive"))
      (node (ref "U1") (pin "98") (pinfunction "P0[2]/TXD0/AD0[7]_98") (pintype "bidirectional"))
    )
    (net (code "74") (name "/VBAT") (class "Default")
      (node (ref "J14") (pin "1") (pinfunction "1_1") (pintype "passive"))
      (node (ref "U1") (pin "19") (pinfunction "VBAT_19") (pintype "power_in"))
    )
    (net (code "75") (name "/VBUS_IF") (class "Default")
      (node (ref "D2") (pin "2") (pinfunction "A_2") (pintype "passive"))
      (node (ref "J9") (pin "1") (pinfunction "1_1") (pintype "passive"))
    )
    (net (code "76") (name "/VBUS_TGT") (class "Default")
      (node (ref "D1") (pin "2") (pinfunction "A_2") (pintype "passive"))
      (node (ref "F1") (pin "2") (pinfunction "2_2") (pintype "power_in"))
    )
    (net (code "77") (name "GND") (class "Default")
      (node (ref "C1") (pin "2") (pinfunction "2_2") (pintype "passive"))
      (node (ref "C10") (pin "2") (pinfunction "2_2") (pintype "passive"))
      (node (ref "C11") (pin "2") (pinfunction "2_2") (pintype "passive"))
      (node (ref "C12") (pin "2") (pinfunction "2_2") (pintype "passive"))
      (node (ref "C13") (pin "2") (pinfunction "2_2") (pintype "passive"))
      (node (ref "C14") (pin "2") (pinfunction "2_2") (pintype "passive"))
      (node (ref "C15") (pin "1") (pinfunction "1_1") (pintype "passive"))
      (node (ref "C2") (pin "2") (pinfunction "2_2") (pintype "passive"))
      (node (ref "C3") (pin "1") (pinfunction "1_1") (pintype "passive"))
      (node (ref "C4") (pin "1") (pinfunction "1_1") (pintype "passive"))
      (node (ref "C5") (pin "1") (pinfunction "1_1") (pintype "passive"))
      (node (ref "C6") (pin "2") (pinfunction "2_2") (pintype "passive"))
      (node (ref "C7") (pin "2") (pinfunction "2_2") (pintype "passive"))
      (node (ref "C8") (pin "2") (pinfunction "2_2") (pintype "passive"))
      (node (ref "C9") (pin "2") (pinfunction "2_2") (pintype "passive"))
      (node (ref "J1") (pin "5") (pinfunction "GND_5") (pintype "passive"))
      (node (ref "J1") (pin "6") (pinfunction "SHIELD_6") (pintype "passive"))
      (node (ref "J1") (pin "7") (pinfunction "SHIELD_7") (pintype "passive"))
      (node (ref "J1") (pin "8") (pinfunction "SHIELD_8") (pintype "passive"))
      (node (ref "J1") (pin "9") (pinfunction "SHIELD_9") (pintype "passive"))
      (node (ref "J10") (pin "1") (pinfunction "1_1") (pintype "passive"))
      (node (ref "J14") (pin "2") (pinfunction "2_2") (pintype "passive"))
      (node (ref "J2") (pin "4") (pinfunction "4_4") (pintype "passive"))
      (node (ref "J3") (pin "1") (pinfunction "1_1") (pintype "passive"))
      (node (ref "J4") (pin "1") (pinfunction "1_1") (pintype "passive"))
      (node (ref "J5") (pin "1") (pinfunction "1_1") (pintype "passive"))
      (node (ref "J6") (pin "1") (pinfunction "1_1") (pintype "passive"))
      (node (ref "J7") (pin "1") (pinfunction "1_1") (pintype "passive"))
      (node (ref "J8") (pin "1") (pinfunction "1_1") (pintype "passive"))
      (node (ref "J9") (pin "8") (pinfunction "8_8") (pintype "passive"))
      (node (ref "R13") (pin "2") (pinfunction "2_2") (pintype "passive"))
      (node (ref "SW1") (pin "P$2") (pinfunction "S_P$2") (pintype "passive"))
      (node (ref "U1") (pin "11") (pinfunction "VSSA_11") (pintype "power_in"))
      (node (ref "U1") (pin "15") (pinfunction "VREFN_15") (pintype "power_in"))
      (node (ref "U1") (pin "31") (pinfunction "VSS_31") (pintype "power_in"))
      (node (ref "U1") (pin "41") (pinfunction "VSS_41") (pintype "power_in"))
      (node (ref "U1") (pin "55") (pinfunction "VSS_55") (pintype "power_in"))
      (node (ref "U1") (pin "72") (pinfunction "VSS_72") (pintype "power_in"))
      (node (ref "U1") (pin "83") (pinfunction "VSS_83") (pintype "power_in"))
      (node (ref "U1") (pin "97") (pinfunction "VSS_97") (pintype "power_in"))
      (node (ref "U2") (pin "1") (pinfunction "GND_1") (pintype "power_in"))
      (node (ref "X1") (pin "P$2") (pinfunction "GND_P$2") (pintype "passive"))
      (node (ref "X1") (pin "P$4") (pinfunction "GND_P$4") (pintype "passive"))
    )
    (net (code "78") (name "Net-(D1-K)") (class "Default")
      (node (ref "C4") (pin "2") (pinfunction "2_2") (pintype "passive"))
      (node (ref "D1") (pin "1") (pinfunction "K_1") (pintype "passive"))
      (node (ref "D2") (pin "1") (pinfunction "K_1") (pintype "passive"))
      (node (ref "U2") (pin "3") (pinfunction "VIN_3") (pintype "power_in"))
    )
    (net (code "79") (name "Net-(J1-D+)") (class "Default")
      (node (ref "J1") (pin "3") (pinfunction "D+_3") (pintype "passive"))
      (node (ref "R11") (pin "2") (pinfunction "2_2") (pintype "passive"))
    )
    (net (code "80") (name "Net-(J1-D-)") (class "Default")
      (node (ref "J1") (pin "2") (pinfunction "D-_2") (pintype "passive"))
      (node (ref "R8") (pin "2") (pinfunction "2_2") (pintype "passive"))
    )
    (net (code "81") (name "Net-(J1-VBUS)") (class "Default")
      (node (ref "F1") (pin "1") (pinfunction "1_1") (pintype "power_in"))
      (node (ref "J1") (pin "1") (pinfunction "VBUS_1") (pintype "passive"))
    )
    (net (code "82") (name "Net-(L1-P$1)") (class "Default")
      (node (ref "C15") (pin "2") (pinfunction "2_2") (pintype "passive"))
      (node (ref "L1") (pin "1") (pinfunction "P$1_1") (pintype "passive"))
      (node (ref "U1") (pin "10") (pinfunction "VDDA_10") (pintype "power_in"))
      (node (ref "U1") (pin "12") (pinfunction "VREFP_12") (pintype "power_in"))
    )
    (net (code "83") (name "Net-(LED1-B)") (class "Default")
      (node (ref "LED1") (pin "2") (pinfunction "B_2") (pintype "passive"))
      (node (ref "R1") (pin "1") (pinfunction "1_1") (pintype "passive"))
    )
    (net (code "84") (name "Net-(LED1-G)") (class "Default")
      (node (ref "LED1") (pin "4") (pinfunction "G_4") (pintype "passive"))
      (node (ref "R3") (pin "1") (pinfunction "1_1") (pintype "passive"))
    )
    (net (code "85") (name "Net-(LED1-R)") (class "Default")
      (node (ref "LED1") (pin "3") (pinfunction "R_3") (pintype "passive"))
      (node (ref "R2") (pin "2") (pinfunction "2_2") (pintype "passive"))
    )
    (net (code "86") (name "Net-(LED2-B)") (class "Default")
      (node (ref "LED2") (pin "2") (pinfunction "B_2") (pintype "passive"))
      (node (ref "R4") (pin "1") (pinfunction "1_1") (pintype "passive"))
    )
    (net (code "87") (name "Net-(LED2-G)") (class "Default")
      (node (ref "LED2") (pin "4") (pinfunction "G_4") (pintype "passive"))
      (node (ref "R6") (pin "1") (pinfunction "1_1") (pintype "passive"))
    )
    (net (code "88") (name "Net-(LED2-R)") (class "Default")
      (node (ref "LED2") (pin "3") (pinfunction "R_3") (pintype "passive"))
      (node (ref "R5") (pin "2") (pinfunction "2_2") (pintype "passive"))
    )
    (net (code "89") (name "Net-(LED3-PadA)") (class "Default")
      (node (ref "LED3") (pin "A") (pinfunction "A_A") (pintype "passive"))
      (node (ref "R12") (pin "2") (pinfunction "2_2") (pintype "passive"))
    )
    (net (code "90") (name "Net-(LED4-PadC)") (class "Default")
      (node (ref "LED4") (pin "C") (pinfunction "C_C") (pintype "passive"))
      (node (ref "R13") (pin "1") (pinfunction "1_1") (pintype "passive"))
    )
    (net (code "91") (name "Net-(LED5-PadA)") (class "Default")
      (node (ref "LED5") (pin "A") (pinfunction "A_A") (pintype "passive"))
      (node (ref "R14") (pin "2") (pinfunction "2_2") (pintype "passive"))
    )
    (net (code "92") (name "Net-(LED6-PadA)") (class "Default")
      (node (ref "LED6") (pin "A") (pinfunction "A_A") (pintype "passive"))
      (node (ref "R15") (pin "2") (pinfunction "2_2") (pintype "passive"))
    )
    (net (code "93") (name "Net-(LED7-PadA)") (class "Default")
      (node (ref "LED7") (pin "A") (pinfunction "A_A") (pintype "passive"))
      (node (ref "R16") (pin "2") (pinfunction "2_2") (pintype "passive"))
    )
    (net (code "94") (name "Net-(Q1-D)") (class "Default")
      (node (ref "Q1") (pin "3") (pinfunction "D_3") (pintype "passive"))
      (node (ref "R7") (pin "2") (pinfunction "2_2") (pintype "passive"))
    )
    (net (code "95") (name "Net-(U1A-P0[0]{slash}RD1{slash}TXD3{slash}SDA1)") (class "Default")
      (node (ref "J2") (pin "2") (pinfunction "2_2") (pintype "passive"))
      (node (ref "R9") (pin "1") (pinfunction "1_1") (pintype "passive"))
      (node (ref "U1") (pin "46") (pinfunction "P0[0]/RD1/TXD3/SDA1_46") (pintype "bidirectional"))
    )
    (net (code "96") (name "Net-(U1A-P0[1]{slash}TD1{slash}RXD3{slash}SCL1)") (class "Default")
      (node (ref "J2") (pin "1") (pinfunction "1_1") (pintype "passive"))
      (node (ref "R10") (pin "1") (pinfunction "1_1") (pintype "passive"))
      (node (ref "U1") (pin "47") (pinfunction "P0[1]/TD1/RXD3/SCL1_47") (pintype "bidirectional"))
    )
    (net (code "97") (name "Net-(U1A-P2[10]{slash}~{EINT0}{slash}NMI)") (class "Default")
      (node (ref "R18") (pin "1") (pinfunction "1_1") (pintype "passive"))
      (node (ref "U1") (pin "53") (pinfunction "P2[10]/~{EINT0}/NMI_53") (pintype "bidirectional"))
    )
    (net (code "98") (name "Net-(U1A-XTAL1)") (class "Default")
      (node (ref "C12") (pin "1") (pinfunction "1_1") (pintype "passive"))
      (node (ref "U1") (pin "22") (pinfunction "XTAL1_22") (pintype "passive"))
      (node (ref "X1") (pin "P$3") (pinfunction "2_P$3") (pintype "passive"))
    )
    (net (code "99") (name "Net-(U1A-XTAL2)") (class "Default")
      (node (ref "C11") (pin "1") (pinfunction "1_1") (pintype "passive"))
      (node (ref "U1") (pin "23") (pinfunction "XTAL2_23") (pintype "passive"))
      (node (ref "X1") (pin "P$1") (pinfunction "1_P$1") (pintype "passive"))
    )
    (net (code "100") (name "VCC_3V3") (class "Default")
      (node (ref "C10") (pin "1") (pinfunction "1_1") (pintype "passive"))
      (node (ref "C3") (pin "2") (pinfunction "2_2") (pintype "passive"))
      (node (ref "C5") (pin "2") (pinfunction "2_2") (pintype "passive"))
      (node (ref "C6") (pin "1") (pinfunction "1_1") (pintype "passive"))
      (node (ref "C7") (pin "1") (pinfunction "1_1") (pintype "passive"))
      (node (ref "C8") (pin "1") (pinfunction "1_1") (pintype "passive"))
      (node (ref "J10") (pin "2") (pinfunction "2_2") (pintype "passive"))
      (node (ref "J2") (pin "3") (pinfunction "3_3") (pintype "passive"))
      (node (ref "J3") (pin "2") (pinfunction "2_2") (pintype "passive"))
      (node (ref "J4") (pin "2") (pinfunction "2_2") (pintype "passive"))
      (node (ref "J5") (pin "2") (pinfunction "2_2") (pintype "passive"))
      (node (ref "J6") (pin "2") (pinfunction "2_2") (pintype "passive"))
      (node (ref "J7") (pin "2") (pinfunction "2_2") (pintype "passive"))
      (node (ref "J8") (pin "2") (pinfunction "2_2") (pintype "passive"))
      (node (ref "L1") (pin "2") (pinfunction "P$2_2") (pintype "passive"))
      (node (ref "LED1") (pin "1") (pinfunction "+_1") (pintype "passive"))
      (node (ref "LED2") (pin "1") (pinfunction "+_1") (pintype "passive"))
      (node (ref "LED4") (pin "A") (pinfunction "A_A") (pintype "passive"))
      (node (ref "Q1") (pin "2") (pinfunction "S_2") (pintype "passive"))
      (node (ref "R10") (pin "2") (pinfunction "2_2") (pintype "passive"))
      (node (ref "R12") (pin "1") (pinfunction "1_1") (pintype "passive"))
      (node (ref "R14") (pin "1") (pinfunction "1_1") (pintype "passive"))
      (node (ref "R15") (pin "1") (pinfunction "1_1") (pintype "passive"))
      (node (ref "R16") (pin "1") (pinfunction "1_1") (pintype "passive"))
      (node (ref "R17") (pin "2") (pinfunction "2_2") (pintype "passive"))
      (node (ref "R18") (pin "2") (pinfunction "2_2") (pintype "passive"))
      (node (ref "R9") (pin "2") (pinfunction "2_2") (pintype "passive"))
      (node (ref "U1") (pin "13") (pinfunction "NC_13") (pintype "passive"))
      (node (ref "U1") (pin "28") (pinfunction "VDD(3V3)_28") (pintype "power_in"))
      (node (ref "U1") (pin "42") (pinfunction "VDD(REG)(3V3)_42") (pintype "power_in"))
      (node (ref "U1") (pin "54") (pinfunction "VDD(3V3)_54") (pintype "power_in"))
      (node (ref "U1") (pin "71") (pinfunction "VDD(3V3)_71") (pintype "power_in"))
      (node (ref "U1") (pin "84") (pinfunction "VDD(REG)(3V3)_84") (pintype "power_in"))
      (node (ref "U1") (pin "96") (pinfunction "VDD(3V3)_96") (pintype "power_in"))
      (node (ref "U2") (pin "2") (pinfunction "VOUT_2") (pintype "power_in"))
      (node (ref "U2") (pin "4") (pinfunction "VOUT_4") (pintype "power_in"))
    )
    (net (code "101") (name "unconnected-(J1-ID-Pad4)") (class "Default")
      (node (ref "J1") (pin "4") (pinfunction "ID_4") (pintype "passive"))
    )
    (net (code "102") (name "unconnected-(U1A-RTCK-Pad100)") (class "Default")
      (node (ref "U1") (pin "100") (pinfunction "RTCK_100") (pintype "output"))
    )
    (net (code "103") (name "unconnected-(U1A-TDI-Pad2)") (class "Default")
      (node (ref "U1") (pin "2") (pinfunction "TDI_2") (pintype "input"))
    )
    (net (code "104") (name "unconnected-(U1A-~{RSTOUT}-Pad14)") (class "Default")
      (node (ref "U1") (pin "14") (pinfunction "~{RSTOUT}_14") (pintype "output"))
    )
    (net (code "105") (name "unconnected-(U1A-~{TRST}-Pad4)") (class "Default")
      (node (ref "U1") (pin "4") (pinfunction "~{TRST}_4") (pintype "input"))
    )
  )
)
